# AS5048A.net
KiCad netlist of a schematic drawn in Altium Designer
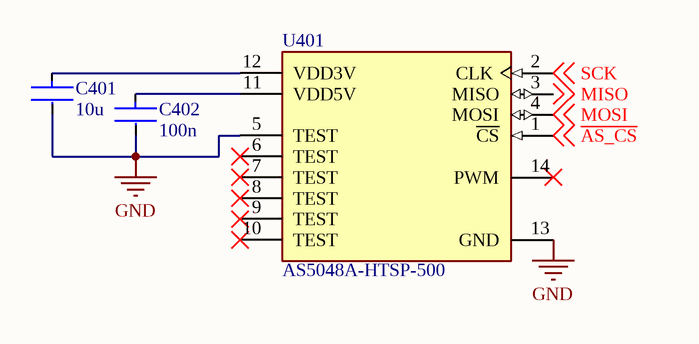
[diagram p0: AS5048A.SchDoc]

(export (version "E")
  (design (tool "Eeschema 10.0.6"))
  (components
    (comp (ref "C401")
      (value "10u")
      (footprint "FP-GRT31C-0_2-IPC_C")
      (description "CAP CER 10UF 50V X5R 1206")
      (fields (field (name "TOLERANCE") "20%"))
      (libsource (lib "Main") (part "GRT31CR61H106ME01L"))
    )
    (comp (ref "C402")
      (value "100n")
      (footprint "FP-GCM155-0_05-MFG")
      (description "Ceramic Capacitor for Automotive 100nF ±10% 50VDC X7R 0402 Paper T/R")
      (fields (field (name "TOLERANCE") "10%"))
      (libsource (lib "Main") (part "GCM155R71H104KE02J"))
    )
    (comp (ref "U401")
      (value "AS5048A-HTSP-500")
      (footprint "TSOP65P640X120-14L")
      (description "SENSOR ANGLE 360DEG SMD")
      (libsource (lib "Main") (part "AS5048A-HTSP-500"))
    )
  )
  (nets
    (net (code "1") (name "AS_CS") (class "Default")
      (node (ref "U401") (pin "1") (pinfunction "~{CS}_1") (pintype "input"))
    )
    (net (code "2") (name "GND") (class "Default")
      (node (ref "C401") (pin "2") (pinfunction "2_2") (pintype "passive"))
      (node (ref "C402") (pin "2") (pinfunction "2_2") (pintype "passive"))
      (node (ref "U401") (pin "13") (pinfunction "GND_13") (pintype "power_in"))
      (node (ref "U401") (pin "5") (pinfunction "TEST_5") (pintype "passive"))
    )
    (net (code "3") (name "MISO") (class "Default")
      (node (ref "U401") (pin "3") (pinfunction "MISO_3") (pintype "bidirectional"))
    )
    (net (code "4") (name "MOSI") (class "Default")
      (node (ref "U401") (pin "4") (pinfunction "MOSI_4") (pintype "bidirectional"))
    )
    (net (code "5") (name "Net-(U401-VDD3V)") (class "Default")
      (node (ref "C401") (pin "1") (pinfunction "1_1") (pintype "passive"))
      (node (ref "U401") (pin "12") (pinfunction "VDD3V_12") (pintype "power_in"))
    )
    (net (code "6") (name "Net-(U401-VDD5V)") (class "Default")
      (node (ref "C402") (pin "1") (pinfunction "1_1") (pintype "passive"))
      (node (ref "U401") (pin "11") (pinfunction "VDD5V_11") (pintype "power_in"))
    )
    (net (code "7") (name "SCK") (class "Default")
      (node (ref "U401") (pin "2") (pinfunction "CLK_2") (pintype "input"))
    )
    (net (code "8") (name "unconnected-(U401-PWM-Pad14)") (class "Default")
      (node (ref "U401") (pin "14") (pinfunction "PWM_14") (pintype "passive+no_connect"))
    )
    (net (code "9") (name "unconnected-(U401-TEST-Pad6)") (class "Default")
      (node (ref "U401") (pin "6") (pinfunction "TEST_6") (pintype "passive+no_connect"))
    )
    (net (code "10") (name "unconnected-(U401-TEST-Pad7)") (class "Default")
      (node (ref "U401") (pin "7") (pinfunction "TEST_7") (pintype "passive+no_connect"))
    )
    (net (code "11") (name "unconnected-(U401-TEST-Pad8)") (class "Default")
      (node (ref "U401") (pin "8") (pinfunction "TEST_8") (pintype "passive+no_connect"))
    )
    (net (code "12") (name "unconnected-(U401-TEST-Pad9)") (class "Default")
      (node (ref "U401") (pin "9") (pinfunction "TEST_9") (pintype "passive+no_connect"))
    )
    (net (code "13") (name "unconnected-(U401-TEST-Pad10)") (class "Default")
      (node (ref "U401") (pin "10") (pinfunction "TEST_10") (pintype "passive+no_connect"))
    )
  )
)
